# POWER_DDR3.net
KiCad netlist of a schematic drawn in Altium Designer
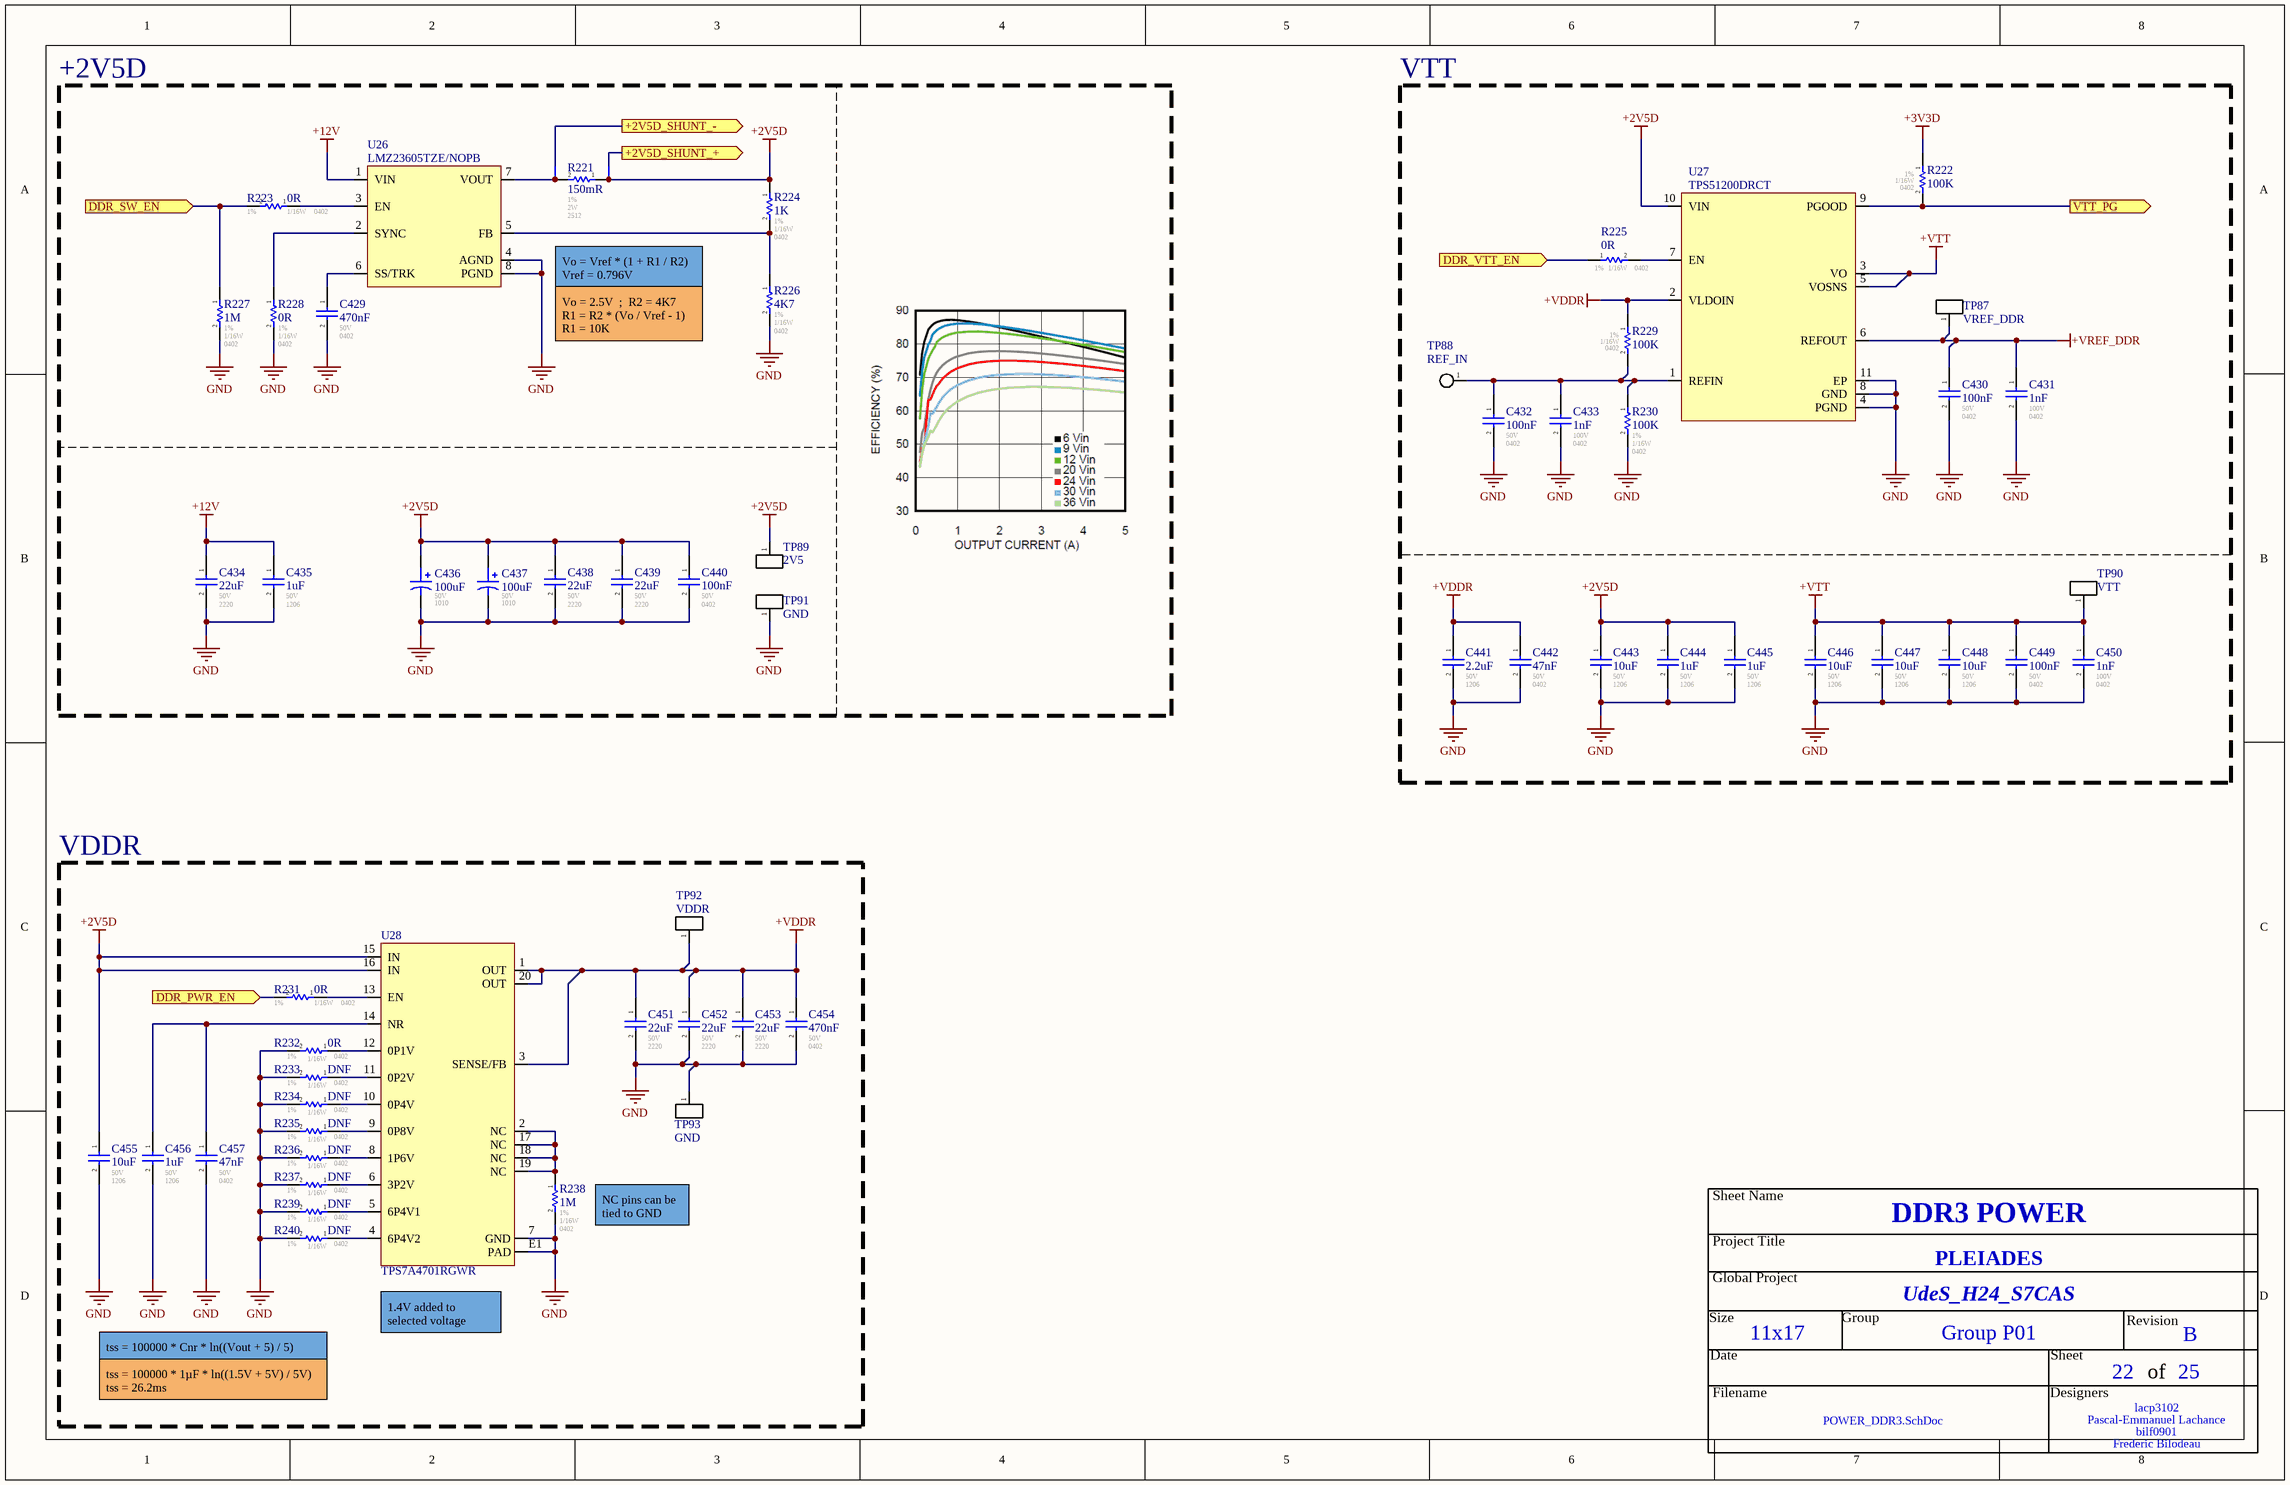
[diagram p0: POWER_DDR3.SchDoc]

(export (version "E")
  (design (tool "Eeschema 10.0.6"))
  (components
    (comp (ref "C429")
      (value "470nF")
      (footprint "0402")
      (description "CGA3E3X7R1H474K080AB\r\n0603 470nF 10% X7R Ceramic Capacitor")
      (fields
        (field (name "MFR") "TDK")
        (field (name "PART#") "CGA3E3X7R1H474K080AB")
        (field (name "VOLTAGE - RATED") "50V")
      )
      (libsource (lib "Symbols") (part "CAP_CER"))
    )
    (comp (ref "C430")
      (value "100nF")
      (footprint "0402")
      (description "GCM155R71H104KE02J\r\n0402 100nF 10% X7R Ceramic Capacitor")
      (fields
        (field (name "MFR") "Murata")
        (field (name "PART#") "GCM155R71H104KE02J")
        (field (name "VOLTAGE - RATED") "50V")
      )
      (libsource (lib "Symbols") (part "CAP_CER"))
    )
    (comp (ref "C431")
      (value "1nF")
      (footprint "0402")
      (description "GCM155R72A102KA37D\r\n0402 1nF 10% X7R Ceramic Capacitor")
      (fields
        (field (name "MFR") "Murata")
        (field (name "PART#") "GCM155R72A102KA37D")
        (field (name "VOLTAGE - RATED") "100V")
      )
      (libsource (lib "Symbols") (part "CAP_CER"))
    )
    (comp (ref "C432")
      (value "100nF")
      (footprint "0402")
      (description "GCM155R71H104KE02J\r\n0402 100nF 10% X7R Ceramic Capacitor")
      (fields
        (field (name "MFR") "Murata")
        (field (name "PART#") "GCM155R71H104KE02J")
        (field (name "VOLTAGE - RATED") "50V")
      )
      (libsource (lib "Symbols") (part "CAP_CER"))
    )
    (comp (ref "C433")
      (value "1nF")
      (footprint "0402")
      (description "GCM155R72A102KA37D\r\n0402 1nF 10% X7R Ceramic Capacitor")
      (fields
        (field (name "MFR") "Murata")
        (field (name "PART#") "GCM155R72A102KA37D")
        (field (name "VOLTAGE - RATED") "100V")
      )
      (libsource (lib "Symbols") (part "CAP_CER"))
    )
    (comp (ref "C434")
      (value "22uF")
      (footprint "2220")
      (description "CGA9P3X7R1H226M250KB\r\n2220 22uF 20% X7R Ceramic Capacitor")
      (fields
        (field (name "MFR") "TDK")
        (field (name "VOLTAGE - RATED") "50V")
        (field (name "TOLERANCE") "20%")
      )
      (libsource (lib "Symbols") (part "CAP_CER"))
    )
    (comp (ref "C435")
      (value "1uF")
      (footprint "1206")
      (description "GCJ31CR71H105KA12L\r\n1206 1uF 10% X7R Ceramic Capacitor")
      (fields
        (field (name "MFR") "Murata")
        (field (name "PART#") "GCJ31CR71H105KA12L")
        (field (name "VOLTAGE - RATED") "50V")
      )
      (libsource (lib "Symbols") (part "CAP_CER"))
    )
    (comp (ref "C436")
      (value "100uF")
      (footprint "CAP_ALU_1010_vishay")
      (description "CAP - ALU 100uF 20% 50V - 1010")
      (fields
        (field (name "MFG") "Vishay Dale")
        (field (name "MFG PART NUMBER") "MAL215099101E3")
        (field (name "VOLTAGE") "50V")
        (field (name "PACKAGE") "1010")
        (field (name "CREATEDBY") "Jonathan Bouchard")
      )
      (libsource (lib "S7CAS_LIB2023") (part "CAP_ALU_MAL215099101E3"))
    )
    (comp (ref "C437")
      (value "100uF")
      (footprint "CAP_ALU_1010_vishay")
      (description "CAP - ALU 100uF 20% 50V - 1010")
      (fields
        (field (name "MFG") "Vishay Dale")
        (field (name "MFG PART NUMBER") "MAL215099101E3")
        (field (name "VOLTAGE") "50V")
        (field (name "PACKAGE") "1010")
        (field (name "CREATEDBY") "Jonathan Bouchard")
      )
      (libsource (lib "S7CAS_LIB2023") (part "CAP_ALU_MAL215099101E3"))
    )
    (comp (ref "C438")
      (value "22uF")
      (footprint "2220")
      (description "CGA9P3X7R1H226M250KB\r\n2220 22uF 20% X7R Ceramic Capacitor")
      (fields
        (field (name "MFR") "TDK")
        (field (name "VOLTAGE - RATED") "50V")
        (field (name "TOLERANCE") "20%")
      )
      (libsource (lib "Symbols") (part "CAP_CER"))
    )
    (comp (ref "C439")
      (value "22uF")
      (footprint "2220")
      (description "CGA9P3X7R1H226M250KB\r\n2220 22uF 20% X7R Ceramic Capacitor")
      (fields
        (field (name "MFR") "TDK")
        (field (name "VOLTAGE - RATED") "50V")
        (field (name "TOLERANCE") "20%")
      )
      (libsource (lib "Symbols") (part "CAP_CER"))
    )
    (comp (ref "C440")
      (value "100nF")
      (footprint "0402")
      (description "GCM155R71H104KE02J\r\n0402 100nF 10% X7R Ceramic Capacitor")
      (fields
        (field (name "MFR") "Murata")
        (field (name "PART#") "GCM155R71H104KE02J")
        (field (name "VOLTAGE - RATED") "50V")
      )
      (libsource (lib "Symbols") (part "CAP_CER"))
    )
    (comp (ref "C441")
      (value "2.2uF")
      (footprint "1206")
      (description "GRT31CR71H225KE13L\r\n1206 2.2uF 10% X7R Ceramic Capacitor")
      (fields
        (field (name "MFR") "Murata")
        (field (name "PART#") "GRT31CR71H225KE13L")
        (field (name "VOLTAGE - RATED") "50V")
      )
      (libsource (lib "Symbols") (part "CAP_CER"))
    )
    (comp (ref "C442")
      (value "47nF")
      (footprint "0402")
      (description "GCM155R71H473KE02J\r\n0402 47nF 10% X7R Ceramic Capacitor")
      (fields
        (field (name "MFR") "Murata")
        (field (name "PART#") "GCM155R71H473KE02J")
        (field (name "VOLTAGE - RATED") "50V")
      )
      (libsource (lib "Symbols") (part "CAP_CER"))
    )
    (comp (ref "C443")
      (value "10uF")
      (footprint "1206")
      (description "GRT31CR61H106KE01L\r\n1206 10uF 10% X5R Ceramic Capacitor")
      (fields
        (field (name "MFR") "Murata")
        (field (name "VOLTAGE - RATED") "50V")
        (field (name "TOLERANCE") "10%")
      )
      (libsource (lib "Symbols") (part "CAP_CER"))
    )
    (comp (ref "C444")
      (value "1uF")
      (footprint "1206")
      (description "GCJ31CR71H105KA12L\r\n1206 1uF 10% X7R Ceramic Capacitor")
      (fields
        (field (name "MFR") "Murata")
        (field (name "PART#") "GCJ31CR71H105KA12L")
        (field (name "VOLTAGE - RATED") "50V")
      )
      (libsource (lib "Symbols") (part "CAP_CER"))
    )
    (comp (ref "C445")
      (value "1uF")
      (footprint "1206")
      (description "GCJ31CR71H105KA12L\r\n1206 1uF 10% X7R Ceramic Capacitor")
      (fields
        (field (name "MFR") "Murata")
        (field (name "PART#") "GCJ31CR71H105KA12L")
        (field (name "VOLTAGE - RATED") "50V")
      )
      (libsource (lib "Symbols") (part "CAP_CER"))
    )
    (comp (ref "C446")
      (value "10uF")
      (footprint "1206")
      (description "GRT31CR61H106KE01L\r\n1206 10uF 10% X5R Ceramic Capacitor")
      (fields
        (field (name "MFR") "Murata")
        (field (name "VOLTAGE - RATED") "50V")
        (field (name "TOLERANCE") "10%")
      )
      (libsource (lib "Symbols") (part "CAP_CER"))
    )
    (comp (ref "C447")
      (value "10uF")
      (footprint "1206")
      (description "GRT31CR61H106KE01L\r\n1206 10uF 10% X5R Ceramic Capacitor")
      (fields
        (field (name "MFR") "Murata")
        (field (name "VOLTAGE - RATED") "50V")
        (field (name "TOLERANCE") "10%")
      )
      (libsource (lib "Symbols") (part "CAP_CER"))
    )
    (comp (ref "C448")
      (value "10uF")
      (footprint "1206")
      (description "GRT31CR61H106KE01L\r\n1206 10uF 10% X5R Ceramic Capacitor")
      (fields
        (field (name "MFR") "Murata")
        (field (name "VOLTAGE - RATED") "50V")
        (field (name "TOLERANCE") "10%")
      )
      (libsource (lib "Symbols") (part "CAP_CER"))
    )
    (comp (ref "C449")
      (value "100nF")
      (footprint "0402")
      (description "GCM155R71H104KE02J\r\n0402 100nF 10% X7R Ceramic Capacitor")
      (fields
        (field (name "MFR") "Murata")
        (field (name "PART#") "GCM155R71H104KE02J")
        (field (name "VOLTAGE - RATED") "50V")
      )
      (libsource (lib "Symbols") (part "CAP_CER"))
    )
    (comp (ref "C450")
      (value "1nF")
      (footprint "0402")
      (description "GCM155R72A102KA37D\r\n0402 1nF 10% X7R Ceramic Capacitor")
      (fields
        (field (name "MFR") "Murata")
        (field (name "PART#") "GCM155R72A102KA37D")
        (field (name "VOLTAGE - RATED") "100V")
      )
      (libsource (lib "Symbols") (part "CAP_CER"))
    )
    (comp (ref "C451")
      (value "22uF")
      (footprint "2220")
      (description "CGA9P3X7R1H226M250KB\r\n2220 22uF 20% X7R Ceramic Capacitor")
      (fields
        (field (name "MFR") "TDK")
        (field (name "VOLTAGE - RATED") "50V")
        (field (name "TOLERANCE") "20%")
      )
      (libsource (lib "Symbols") (part "CAP_CER"))
    )
    (comp (ref "C452")
      (value "22uF")
      (footprint "2220")
      (description "CGA9P3X7R1H226M250KB\r\n2220 22uF 20% X7R Ceramic Capacitor")
      (fields
        (field (name "MFR") "TDK")
        (field (name "VOLTAGE - RATED") "50V")
        (field (name "TOLERANCE") "20%")
      )
      (libsource (lib "Symbols") (part "CAP_CER"))
    )
    (comp (ref "C453")
      (value "22uF")
      (footprint "2220")
      (description "CGA9P3X7R1H226M250KB\r\n2220 22uF 20% X7R Ceramic Capacitor")
      (fields
        (field (name "MFR") "TDK")
        (field (name "VOLTAGE - RATED") "50V")
        (field (name "TOLERANCE") "20%")
      )
      (libsource (lib "Symbols") (part "CAP_CER"))
    )
    (comp (ref "C454")
      (value "470nF")
      (footprint "0402")
      (description "CGA3E3X7R1H474K080AB\r\n0603 470nF 10% X7R Ceramic Capacitor")
      (fields
        (field (name "MFR") "TDK")
        (field (name "PART#") "CGA3E3X7R1H474K080AB")
        (field (name "VOLTAGE - RATED") "50V")
      )
      (libsource (lib "Symbols") (part "CAP_CER"))
    )
    (comp (ref "C455")
      (value "10uF")
      (footprint "1206")
      (description "GRT31CR61H106KE01L\r\n1206 10uF 10% X5R Ceramic Capacitor")
      (fields
        (field (name "MFR") "Murata")
        (field (name "VOLTAGE - RATED") "50V")
        (field (name "TOLERANCE") "10%")
      )
      (libsource (lib "Symbols") (part "CAP_CER"))
    )
    (comp (ref "C456")
      (value "1uF")
      (footprint "1206")
      (description "GCJ31CR71H105KA12L\r\n1206 1uF 10% X7R Ceramic Capacitor")
      (fields
        (field (name "MFR") "Murata")
        (field (name "PART#") "GCJ31CR71H105KA12L")
        (field (name "VOLTAGE - RATED") "50V")
      )
      (libsource (lib "Symbols") (part "CAP_CER"))
    )
    (comp (ref "C457")
      (value "47nF")
      (footprint "0402")
      (description "GCM155R71H473KE02J\r\n0402 47nF 10% X7R Ceramic Capacitor")
      (fields
        (field (name "MFR") "Murata")
        (field (name "PART#") "GCM155R71H473KE02J")
        (field (name "VOLTAGE - RATED") "50V")
      )
      (libsource (lib "Symbols") (part "CAP_CER"))
    )
    (comp (ref "NT44")
      (value "Net Tie")
      (footprint "NETTIE_5")
      (libsource (lib "Symbols") (part "NET_TIE_SMALL"))
    )
    (comp (ref "NT45")
      (value "Net Tie")
      (footprint "NETTIE_5")
      (libsource (lib "Symbols") (part "NET_TIE_SMALL"))
    )
    (comp (ref "R221")
      (value "150mR")
      (footprint "RES_2512")
      (description "CSRN2512FKR150")
      (fields
        (field (name "TOLERANCE") "1%")
        (field (name "POWER") "2W")
        (field (name "PACKAGE / CASE") "2512")
      )
      (libsource (lib "Symbols") (part "RESISTOR"))
    )
    (comp (ref "R222")
      (value "100K")
      (footprint "RES_0402")
      (fields
        (field (name "TOLERANCE") "1%")
        (field (name "POWER") "1/16W")
        (field (name "PACKAGE / CASE") "0402")
      )
      (libsource (lib "Symbols") (part "RESISTOR"))
    )
    (comp (ref "R223")
      (value "0R")
      (footprint "RES_0402")
      (fields
        (field (name "TOLERANCE") "1%")
        (field (name "POWER") "1/16W")
        (field (name "PACKAGE / CASE") "0402")
      )
      (libsource (lib "Symbols") (part "RESISTOR"))
    )
    (comp (ref "R224")
      (value "1K")
      (footprint "RES_0402")
      (fields
        (field (name "TOLERANCE") "1%")
        (field (name "POWER") "1/16W")
        (field (name "PACKAGE / CASE") "0402")
      )
      (libsource (lib "Symbols") (part "RESISTOR"))
    )
    (comp (ref "R225")
      (value "0R")
      (footprint "RES_0402")
      (fields
        (field (name "TOLERANCE") "1%")
        (field (name "POWER") "1/16W")
        (field (name "PACKAGE / CASE") "0402")
      )
      (libsource (lib "Symbols") (part "RESISTOR"))
    )
    (comp (ref "R226")
      (value "4K7")
      (footprint "RES_0402")
      (fields
        (field (name "TOLERANCE") "1%")
        (field (name "POWER") "1/16W")
        (field (name "PACKAGE / CASE") "0402")
      )
      (libsource (lib "Symbols") (part "RESISTOR"))
    )
    (comp (ref "R227")
      (value "1M")
      (footprint "RES_0402")
      (description "1M 0402 1% 1/16W Resistor")
      (fields
        (field (name "TOLERANCE") "1%")
        (field (name "POWER") "1/16W")
        (field (name "PACKAGE / CASE") "0402")
      )
      (libsource (lib "Symbols") (part "RESISTOR"))
    )
    (comp (ref "R228")
      (value "0R")
      (footprint "RES_0402")
      (fields
        (field (name "TOLERANCE") "1%")
        (field (name "POWER") "1/16W")
        (field (name "PACKAGE / CASE") "0402")
      )
      (libsource (lib "Symbols") (part "RESISTOR"))
    )
    (comp (ref "R229")
      (value "100K")
      (footprint "RES_0402")
      (fields
        (field (name "TOLERANCE") "1%")
        (field (name "POWER") "1/16W")
        (field (name "PACKAGE / CASE") "0402")
      )
      (libsource (lib "Symbols") (part "RESISTOR"))
    )
    (comp (ref "R230")
      (value "100K")
      (footprint "RES_0402")
      (fields
        (field (name "TOLERANCE") "1%")
        (field (name "POWER") "1/16W")
        (field (name "PACKAGE / CASE") "0402")
      )
      (libsource (lib "Symbols") (part "RESISTOR"))
    )
    (comp (ref "R231")
      (value "0R")
      (footprint "RES_0402")
      (fields
        (field (name "TOLERANCE") "1%")
        (field (name "POWER") "1/16W")
        (field (name "PACKAGE / CASE") "0402")
      )
      (libsource (lib "Symbols") (part "RESISTOR"))
    )
    (comp (ref "R232")
      (value "0R")
      (footprint "RES_0402")
      (fields
        (field (name "TOLERANCE") "1%")
        (field (name "POWER") "1/16W")
        (field (name "PACKAGE / CASE") "0402")
      )
      (libsource (lib "Symbols") (part "RESISTOR"))
    )
    (comp (ref "R233")
      (value "DNF")
      (footprint "RES_0402")
      (fields
        (field (name "TOLERANCE") "1%")
        (field (name "POWER") "1/16W")
        (field (name "PACKAGE / CASE") "0402")
      )
      (libsource (lib "Symbols") (part "RESISTOR"))
    )
    (comp (ref "R234")
      (value "DNF")
      (footprint "RES_0402")
      (fields
        (field (name "TOLERANCE") "1%")
        (field (name "POWER") "1/16W")
        (field (name "PACKAGE / CASE") "0402")
      )
      (libsource (lib "Symbols") (part "RESISTOR"))
    )
    (comp (ref "R235")
      (value "DNF")
      (footprint "RES_0402")
      (fields
        (field (name "TOLERANCE") "1%")
        (field (name "POWER") "1/16W")
        (field (name "PACKAGE / CASE") "0402")
      )
      (libsource (lib "Symbols") (part "RESISTOR"))
    )
    (comp (ref "R236")
      (value "DNF")
      (footprint "RES_0402")
      (fields
        (field (name "TOLERANCE") "1%")
        (field (name "POWER") "1/16W")
        (field (name "PACKAGE / CASE") "0402")
      )
      (libsource (lib "Symbols") (part "RESISTOR"))
    )
    (comp (ref "R237")
      (value "DNF")
      (footprint "RES_0402")
      (fields
        (field (name "TOLERANCE") "1%")
        (field (name "POWER") "1/16W")
        (field (name "PACKAGE / CASE") "0402")
      )
      (libsource (lib "Symbols") (part "RESISTOR"))
    )
    (comp (ref "R238")
      (value "1M")
      (footprint "RES_0402")
      (description "1M 0402 1% 1/16W Resistor")
      (fields
        (field (name "TOLERANCE") "1%")
        (field (name "POWER") "1/16W")
        (field (name "PACKAGE / CASE") "0402")
      )
      (libsource (lib "Symbols") (part "RESISTOR"))
    )
    (comp (ref "R239")
      (value "DNF")
      (footprint "RES_0402")
      (fields
        (field (name "TOLERANCE") "1%")
        (field (name "POWER") "1/16W")
        (field (name "PACKAGE / CASE") "0402")
      )
      (libsource (lib "Symbols") (part "RESISTOR"))
    )
    (comp (ref "R240")
      (value "DNF")
      (footprint "RES_0402")
      (fields
        (field (name "TOLERANCE") "1%")
        (field (name "POWER") "1/16W")
        (field (name "PACKAGE / CASE") "0402")
      )
      (libsource (lib "Symbols") (part "RESISTOR"))
    )
    (comp (ref "TP87")
      (value "VREF_DDR")
      (footprint "TP_HOLE")
      (description "Test Point")
      (libsource (lib "Symbols") (part "TESTPOINT"))
    )
    (comp (ref "TP88")
      (value "REF_IN")
      (footprint "TP_PAD_SMALL")
      (description "Test Point")
      (libsource (lib "Symbols") (part "TESTPOINT_PAD_SMALL"))
    )
    (comp (ref "TP89")
      (value "2V5")
      (footprint "TP_HOLE")
      (description "Test Point")
      (libsource (lib "Symbols") (part "TESTPOINT"))
    )
    (comp (ref "TP90")
      (value "VTT")
      (footprint "TP_HOLE")
      (description "Test Point")
      (libsource (lib "Symbols") (part "TESTPOINT"))
    )
    (comp (ref "TP91")
      (value "GND")
      (footprint "TP_HOLE")
      (description "Test Point")
      (libsource (lib "Symbols") (part "TESTPOINT"))
    )
    (comp (ref "TP92")
      (value "VDDR")
      (footprint "TP_HOLE")
      (description "Test Point")
      (libsource (lib "Symbols") (part "TESTPOINT"))
    )
    (comp (ref "TP93")
      (value "GND")
      (footprint "TP_HOLE")
      (description "Test Point")
      (libsource (lib "Symbols") (part "TESTPOINT"))
    )
    (comp (ref "U26")
      (value "LMZ23605TZE/NOPB")
      (footprint "REG_SWR_LMZ23605TZE/NOPB")
      (description "REG - IC BUCK SYNC 36V 5A - TO-PMOD-7")
      (fields
        (field (name "CREATEDBY/DATE") "Arnaud Samson - 05/07/18")
        (field (name "VERIFIEDBY") "Jonathan Bouchard 2018-07-13")
      )
      (libsource (lib "S7CAS_LIB2023") (part "REG_SWR_LMZ23605TZE/NOPB"))
    )
    (comp (ref "U27")
      (value "TPS51200DRCT")
      (footprint "REG_PMIC_TPS51200DRCT")
      (description "REG - DDR TERMINATION/REF REG - 10-VFDFN")
      (fields
        (field (name "CREATEDBY/DATE") "Joel Lemay 2019-03-19")
        (field (name "VERIFIEDBY") "Nicolas V. (2019-05-31)")
      )
      (libsource (lib "S7CAS_LIB2023") (part "REG_PMIC_TPS51200DRCT"))
    )
    (comp (ref "U28")
      (value "TPS7A4701RGWR")
      (footprint "REG_TPS7A4701RGWR")
      (description "REG - LINEAR POS ADJ 1A - 20VQFN")
      (fields
        (field (name "CREATEDBY/DATE") "L-P Gauthier / 2018-05-29")
        (field (name "VERIFIEDBY") "Caroline Paulin - 28 sept 2018")
      )
      (libsource (lib "S7CAS_LIB2023") (part "REG_LDO_TPS7A4701RGWR"))
    )
  )
  (nets
    (net (code "1") (name "+2V5D") (class "Default")
      (node (ref "C436") (pin "1") (pinfunction "1_1") (pintype "passive"))
      (node (ref "C437") (pin "1") (pinfunction "1_1") (pintype "passive"))
      (node (ref "C438") (pin "1") (pinfunction "1_1") (pintype "passive"))
      (node (ref "C439") (pin "1") (pinfunction "1_1") (pintype "passive"))
      (node (ref "C440") (pin "1") (pinfunction "1_1") (pintype "passive"))
      (node (ref "C443") (pin "1") (pinfunction "1_1") (pintype "passive"))
      (node (ref "C444") (pin "1") (pinfunction "1_1") (pintype "passive"))
      (node (ref "C445") (pin "1") (pinfunction "1_1") (pintype "passive"))
      (node (ref "C455") (pin "1") (pinfunction "1_1") (pintype "passive"))
      (node (ref "NT45") (pin "1") (pinfunction "1_1") (pintype "passive"))
      (node (ref "R221") (pin "1") (pinfunction "1_1") (pintype "passive"))
      (node (ref "R224") (pin "1") (pinfunction "1_1") (pintype "passive"))
      (node (ref "TP89") (pin "1") (pinfunction "A_1") (pintype "passive"))
      (node (ref "U27") (pin "10") (pinfunction "VIN_10") (pintype "passive"))
      (node (ref "U28") (pin "15") (pinfunction "IN_15") (pintype "passive"))
      (node (ref "U28") (pin "16") (pinfunction "IN_16") (pintype "passive"))
    )
    (net (code "2") (name "+3V3D") (class "Default")
      (node (ref "R222") (pin "1") (pinfunction "1_1") (pintype "passive"))
    )
    (net (code "3") (name "+12V") (class "Default")
      (node (ref "C434") (pin "1") (pinfunction "1_1") (pintype "passive"))
      (node (ref "C435") (pin "1") (pinfunction "1_1") (pintype "passive"))
      (node (ref "U26") (pin "1") (pinfunction "VIN_1") (pintype "passive"))
    )
    (net (code "4") (name "+VDDR") (class "Default")
      (node (ref "C441") (pin "1") (pinfunction "1_1") (pintype "passive"))
      (node (ref "C442") (pin "1") (pinfunction "1_1") (pintype "passive"))
      (node (ref "C451") (pin "1") (pinfunction "1_1") (pintype "passive"))
      (node (ref "C452") (pin "1") (pinfunction "1_1") (pintype "passive"))
      (node (ref "C453") (pin "1") (pinfunction "1_1") (pintype "passive"))
      (node (ref "C454") (pin "1") (pinfunction "1_1") (pintype "passive"))
      (node (ref "R229") (pin "1") (pinfunction "1_1") (pintype "passive"))
      (node (ref "TP92") (pin "1") (pinfunction "A_1") (pintype "passive"))
      (node (ref "U27") (pin "2") (pinfunction "VLDOIN_2") (pintype "passive"))
      (node (ref "U28") (pin "1") (pinfunction "OUT_1") (pintype "passive"))
      (node (ref "U28") (pin "20") (pinfunction "OUT_20") (pintype "passive"))
      (node (ref "U28") (pin "3") (pinfunction "SENSE/FB_3") (pintype "passive"))
    )
    (net (code "5") (name "+VREF_DDR") (class "Default")
      (node (ref "C430") (pin "1") (pinfunction "1_1") (pintype "passive"))
      (node (ref "C431") (pin "1") (pinfunction "1_1") (pintype "passive"))
      (node (ref "TP87") (pin "1") (pinfunction "A_1") (pintype "passive"))
      (node (ref "U27") (pin "6") (pinfunction "REFOUT_6") (pintype "passive"))
    )
    (net (code "6") (name "+VTT") (class "Default")
      (node (ref "C446") (pin "1") (pinfunction "1_1") (pintype "passive"))
      (node (ref "C447") (pin "1") (pinfunction "1_1") (pintype "passive"))
      (node (ref "C448") (pin "1") (pinfunction "1_1") (pintype "passive"))
      (node (ref "C449") (pin "1") (pinfunction "1_1") (pintype "passive"))
      (node (ref "C450") (pin "1") (pinfunction "1_1") (pintype "passive"))
      (node (ref "TP90") (pin "1") (pinfunction "A_1") (pintype "passive"))
      (node (ref "U27") (pin "3") (pinfunction "VO_3") (pintype "passive"))
      (node (ref "U27") (pin "5") (pinfunction "VOSNS_5") (pintype "passive"))
    )
    (net (code "7") (name "/+2V5D_SHUNT_+") (class "Default")
      (node (ref "NT45") (pin "2") (pinfunction "2_2") (pintype "passive"))
    )
    (net (code "8") (name "/+2V5D_SHUNT_-") (class "Default")
      (node (ref "NT44") (pin "2") (pinfunction "2_2") (pintype "passive"))
    )
    (net (code "9") (name "/DDR_PWR_EN") (class "Default")
      (node (ref "R231") (pin "2") (pinfunction "2_2") (pintype "passive"))
    )
    (net (code "10") (name "/DDR_SW_EN") (class "Default")
      (node (ref "R223") (pin "2") (pinfunction "2_2") (pintype "passive"))
      (node (ref "R227") (pin "1") (pinfunction "1_1") (pintype "passive"))
    )
    (net (code "11") (name "/DDR_VTT_EN") (class "Default")
      (node (ref "R225") (pin "1") (pinfunction "1_1") (pintype "passive"))
    )
    (net (code "12") (name "/VTT_PG") (class "Default")
      (node (ref "R222") (pin "2") (pinfunction "2_2") (pintype "passive"))
      (node (ref "U27") (pin "9") (pinfunction "PGOOD_9") (pintype "passive"))
    )
    (net (code "13") (name "GND") (class "Default")
      (node (ref "C429") (pin "2") (pinfunction "2_2") (pintype "passive"))
      (node (ref "C430") (pin "2") (pinfunction "2_2") (pintype "passive"))
      (node (ref "C431") (pin "2") (pinfunction "2_2") (pintype "passive"))
      (node (ref "C432") (pin "2") (pinfunction "2_2") (pintype "passive"))
      (node (ref "C433") (pin "2") (pinfunction "2_2") (pintype "passive"))
      (node (ref "C434") (pin "2") (pinfunction "2_2") (pintype "passive"))
      (node (ref "C435") (pin "2") (pinfunction "2_2") (pintype "passive"))
      (node (ref "C436") (pin "2") (pinfunction "2_2") (pintype "passive"))
      (node (ref "C437") (pin "2") (pinfunction "2_2") (pintype "passive"))
      (node (ref "C438") (pin "2") (pinfunction "2_2") (pintype "passive"))
      (node (ref "C439") (pin "2") (pinfunction "2_2") (pintype "passive"))
      (node (ref "C440") (pin "2") (pinfunction "2_2") (pintype "passive"))
      (node (ref "C441") (pin "2") (pinfunction "2_2") (pintype "passive"))
      (node (ref "C442") (pin "2") (pinfunction "2_2") (pintype "passive"))
      (node (ref "C443") (pin "2") (pinfunction "2_2") (pintype "passive"))
      (node (ref "C444") (pin "2") (pinfunction "2_2") (pintype "passive"))
      (node (ref "C445") (pin "2") (pinfunction "2_2") (pintype "passive"))
      (node (ref "C446") (pin "2") (pinfunction "2_2") (pintype "passive"))
      (node (ref "C447") (pin "2") (pinfunction "2_2") (pintype "passive"))
      (node (ref "C448") (pin "2") (pinfunction "2_2") (pintype "passive"))
      (node (ref "C449") (pin "2") (pinfunction "2_2") (pintype "passive"))
      (node (ref "C450") (pin "2") (pinfunction "2_2") (pintype "passive"))
      (node (ref "C451") (pin "2") (pinfunction "2_2") (pintype "passive"))
      (node (ref "C452") (pin "2") (pinfunction "2_2") (pintype "passive"))
      (node (ref "C453") (pin "2") (pinfunction "2_2") (pintype "passive"))
      (node (ref "C454") (pin "2") (pinfunction "2_2") (pintype "passive"))
      (node (ref "C455") (pin "2") (pinfunction "2_2") (pintype "passive"))
      (node (ref "C456") (pin "2") (pinfunction "2_2") (pintype "passive"))
      (node (ref "C457") (pin "2") (pinfunction "2_2") (pintype "passive"))
      (node (ref "R226") (pin "2") (pinfunction "2_2") (pintype "passive"))
      (node (ref "R227") (pin "2") (pinfunction "2_2") (pintype "passive"))
      (node (ref "R228") (pin "2") (pinfunction "2_2") (pintype "passive"))
      (node (ref "R230") (pin "2") (pinfunction "2_2") (pintype "passive"))
      (node (ref "R232") (pin "2") (pinfunction "2_2") (pintype "passive"))
      (node (ref "R233") (pin "2") (pinfunction "2_2") (pintype "passive"))
      (node (ref "R234") (pin "2") (pinfunction "2_2") (pintype "passive"))
      (node (ref "R235") (pin "2") (pinfunction "2_2") (pintype "passive"))
      (node (ref "R236") (pin "2") (pinfunction "2_2") (pintype "passive"))
      (node (ref "R237") (pin "2") (pinfunction "2_2") (pintype "passive"))
      (node (ref "R238") (pin "2") (pinfunction "2_2") (pintype "passive"))
      (node (ref "R239") (pin "2") (pinfunction "2_2") (pintype "passive"))
      (node (ref "R240") (pin "2") (pinfunction "2_2") (pintype "passive"))
      (node (ref "TP91") (pin "1") (pinfunction "A_1") (pintype "passive"))
      (node (ref "TP93") (pin "1") (pinfunction "A_1") (pintype "passive"))
      (node (ref "U26") (pin "4") (pinfunction "AGND_4") (pintype "passive"))
      (node (ref "U26") (pin "8") (pinfunction "PGND_8") (pintype "passive"))
      (node (ref "U27") (pin "11") (pinfunction "EP_11") (pintype "passive"))
      (node (ref "U27") (pin "4") (pinfunction "PGND_4") (pintype "passive"))
      (node (ref "U27") (pin "8") (pinfunction "GND_8") (pintype "passive"))
      (node (ref "U28") (pin "7") (pinfunction "GND_7") (pintype "passive"))
      (node (ref "U28") (pin "E1") (pinfunction "PAD_E1") (pintype "passive"))
    )
    (net (code "14") (name "Net-(R238-Pad1)") (class "Default")
      (node (ref "R238") (pin "1") (pinfunction "1_1") (pintype "passive"))
      (node (ref "U28") (pin "17") (pinfunction "NC_17") (pintype "passive"))
      (node (ref "U28") (pin "18") (pinfunction "NC_18") (pintype "passive"))
      (node (ref "U28") (pin "19") (pinfunction "NC_19") (pintype "passive"))
      (node (ref "U28") (pin "2") (pinfunction "NC_2") (pintype "passive"))
    )
    (net (code "15") (name "Net-(TP88-A)") (class "Default")
      (node (ref "C432") (pin "1") (pinfunction "1_1") (pintype "passive"))
      (node (ref "C433") (pin "1") (pinfunction "1_1") (pintype "passive"))
      (node (ref "R229") (pin "2") (pinfunction "2_2") (pintype "passive"))
      (node (ref "R230") (pin "1") (pinfunction "1_1") (pintype "passive"))
      (node (ref "TP88") (pin "1") (pinfunction "A_1") (pintype "passive"))
      (node (ref "U27") (pin "1") (pinfunction "REFIN_1") (pintype "passive"))
    )
    (net (code "16") (name "Net-(U26-EN)") (class "Default")
      (node (ref "R223") (pin "1") (pinfunction "1_1") (pintype "passive"))
      (node (ref "U26") (pin "3") (pinfunction "EN_3") (pintype "passive"))
    )
    (net (code "17") (name "Net-(U26-FB)") (class "Default")
      (node (ref "R224") (pin "2") (pinfunction "2_2") (pintype "passive"))
      (node (ref "R226") (pin "1") (pinfunction "1_1") (pintype "passive"))
      (node (ref "U26") (pin "5") (pinfunction "FB_5") (pintype "passive"))
    )
    (net (code "18") (name "Net-(U26-SS{slash}TRK)") (class "Default")
      (node (ref "C429") (pin "1") (pinfunction "1_1") (pintype "passive"))
      (node (ref "U26") (pin "6") (pinfunction "SS/TRK_6") (pintype "passive"))
    )
    (net (code "19") (name "Net-(U26-SYNC)") (class "Default")
      (node (ref "R228") (pin "1") (pinfunction "1_1") (pintype "passive"))
      (node (ref "U26") (pin "2") (pinfunction "SYNC_2") (pintype "passive"))
    )
    (net (code "20") (name "Net-(U26-VOUT)") (class "Default")
      (node (ref "NT44") (pin "1") (pinfunction "1_1") (pintype "passive"))
      (node (ref "R221") (pin "2") (pinfunction "2_2") (pintype "passive"))
      (node (ref "U26") (pin "7") (pinfunction "VOUT_7") (pintype "passive"))
    )
    (net (code "21") (name "Net-(U27-EN)") (class "Default")
      (node (ref "R225") (pin "2") (pinfunction "2_2") (pintype "passive"))
      (node (ref "U27") (pin "7") (pinfunction "EN_7") (pintype "passive"))
    )
    (net (code "22") (name "Net-(U28-0P1V)") (class "Default")
      (node (ref "R232") (pin "1") (pinfunction "1_1") (pintype "passive"))
      (node (ref "U28") (pin "12") (pinfunction "0P1V_12") (pintype "passive"))
    )
    (net (code "23") (name "Net-(U28-0P2V)") (class "Default")
      (node (ref "R233") (pin "1") (pinfunction "1_1") (pintype "passive"))
      (node (ref "U28") (pin "11") (pinfunction "0P2V_11") (pintype "passive"))
    )
    (net (code "24") (name "Net-(U28-0P4V)") (class "Default")
      (node (ref "R234") (pin "1") (pinfunction "1_1") (pintype "passive"))
      (node (ref "U28") (pin "10") (pinfunction "0P4V_10") (pintype "passive"))
    )
    (net (code "25") (name "Net-(U28-0P8V)") (class "Default")
      (node (ref "R235") (pin "1") (pinfunction "1_1") (pintype "passive"))
      (node (ref "U28") (pin "9") (pinfunction "0P8V_9") (pintype "passive"))
    )
    (net (code "26") (name "Net-(U28-1P6V)") (class "Default")
      (node (ref "R236") (pin "1") (pinfunction "1_1") (pintype "passive"))
      (node (ref "U28") (pin "8") (pinfunction "1P6V_8") (pintype "passive"))
    )
    (net (code "27") (name "Net-(U28-3P2V)") (class "Default")
      (node (ref "R237") (pin "1") (pinfunction "1_1") (pintype "passive"))
      (node (ref "U28") (pin "6") (pinfunction "3P2V_6") (pintype "passive"))
    )
    (net (code "28") (name "Net-(U28-6P4V1)") (class "Default")
      (node (ref "R239") (pin "1") (pinfunction "1_1") (pintype "passive"))
      (node (ref "U28") (pin "5") (pinfunction "6P4V1_5") (pintype "passive"))
    )
    (net (code "29") (name "Net-(U28-6P4V2)") (class "Default")
      (node (ref "R240") (pin "1") (pinfunction "1_1") (pintype "passive"))
      (node (ref "U28") (pin "4") (pinfunction "6P4V2_4") (pintype "passive"))
    )
    (net (code "30") (name "Net-(U28-EN)") (class "Default")
      (node (ref "R231") (pin "1") (pinfunction "1_1") (pintype "passive"))
      (node (ref "U28") (pin "13") (pinfunction "EN_13") (pintype "passive"))
    )
    (net (code "31") (name "Net-(U28-NR)") (class "Default")
      (node (ref "C456") (pin "1") (pinfunction "1_1") (pintype "passive"))
      (node (ref "C457") (pin "1") (pinfunction "1_1") (pintype "passive"))
      (node (ref "U28") (pin "14") (pinfunction "NR_14") (pintype "passive"))
    )
  )
)
